# Device_1_ver1_1.net
KiCad netlist of a schematic drawn in EAGLE
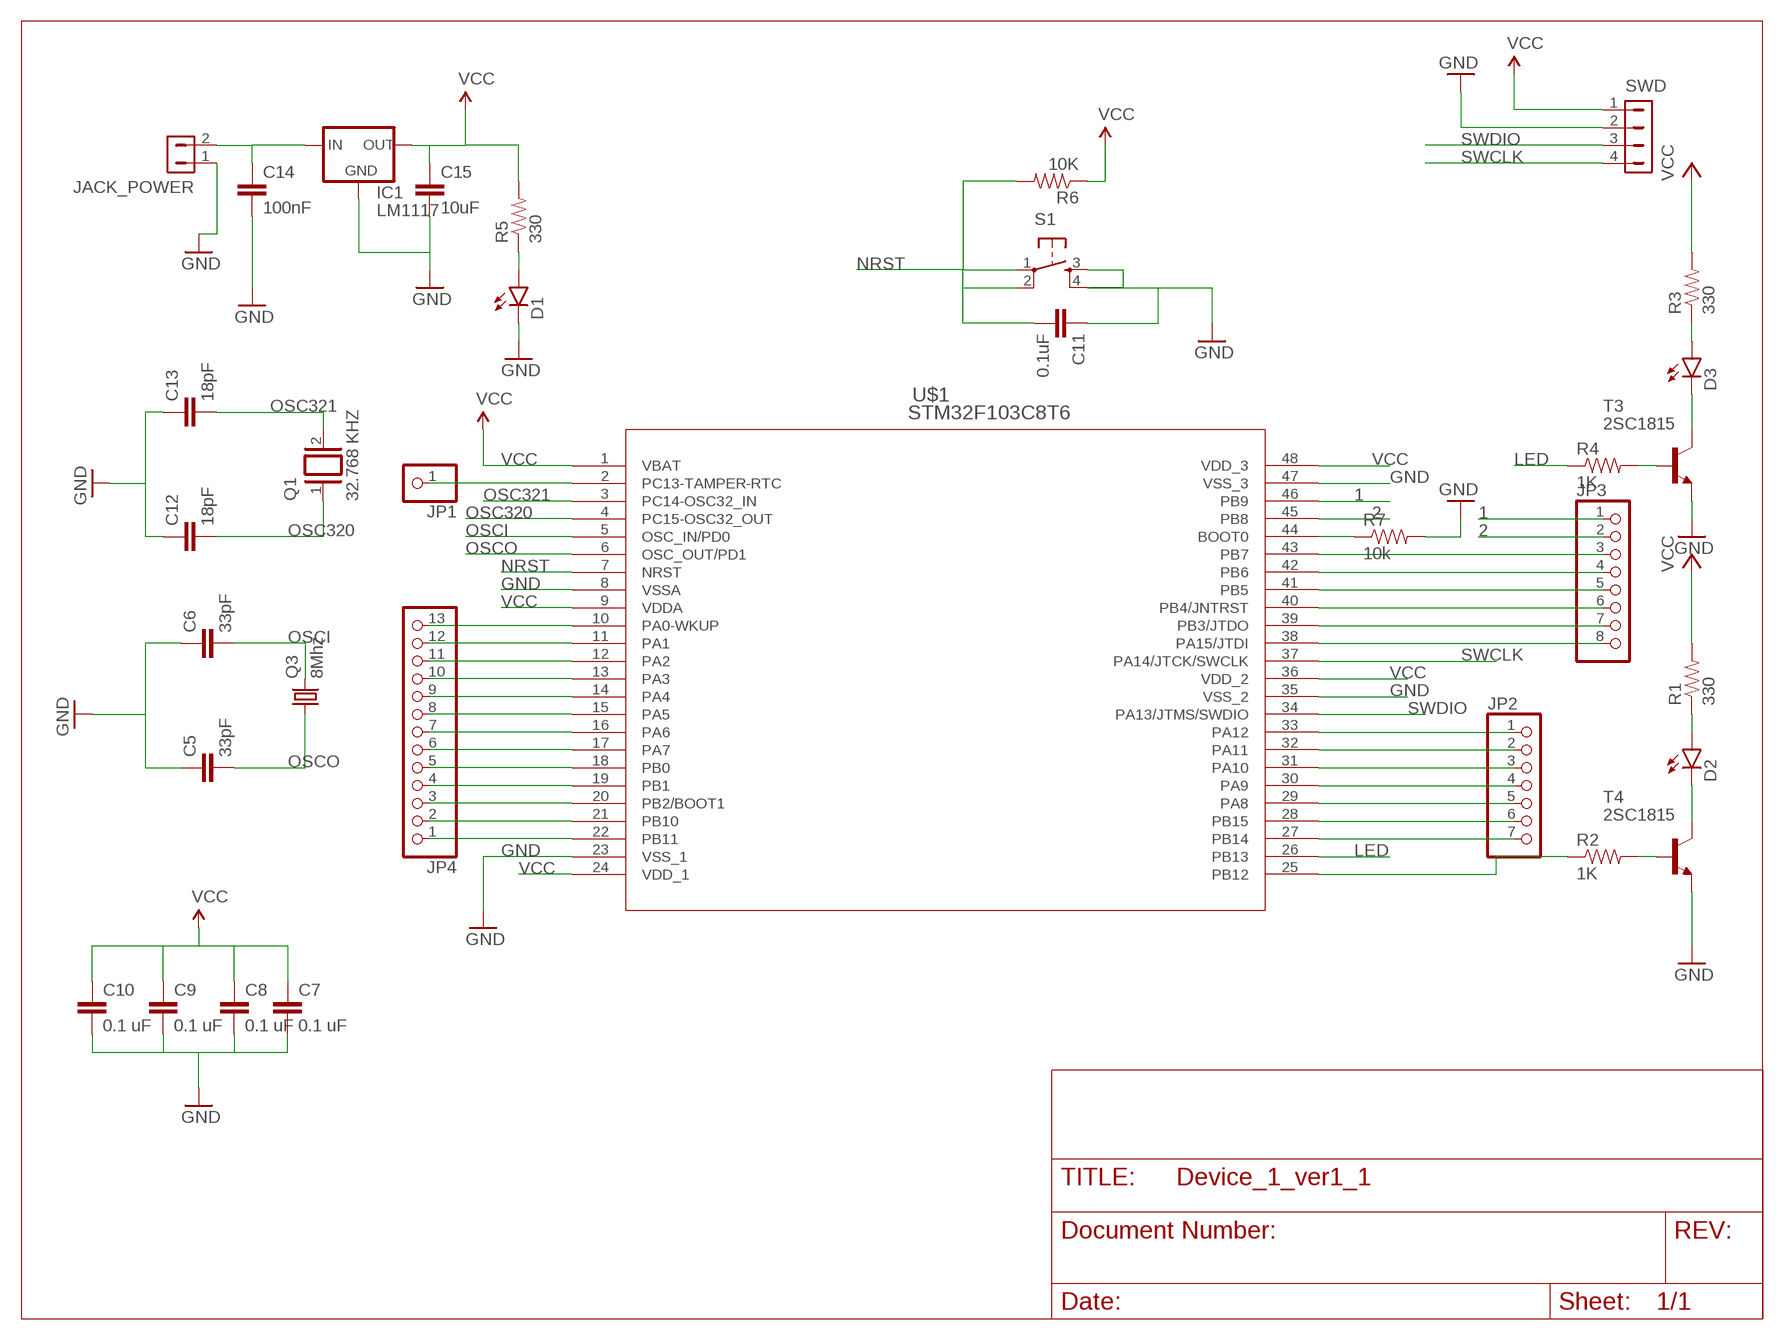
[diagram p0: schematic, sheet 1]

(export (version "E")
  (design (tool "Eeschema 10.0.6"))
  (components
    (comp (ref "C5")
      (value "33pF")
      (footprint "eagle-import:CAP-PTH-SMALL")
      (libsource (lib "eagle-import") (part "CAPPTH"))
    )
    (comp (ref "C6")
      (value "33pF")
      (footprint "eagle-import:CAP-PTH-SMALL")
      (libsource (lib "eagle-import") (part "CAPPTH"))
    )
    (comp (ref "C7")
      (value "0.1 uF")
      (footprint "eagle-import:CAP-PTH-SMALL")
      (libsource (lib "eagle-import") (part "CAPPTH"))
    )
    (comp (ref "C8")
      (value "0.1 uF")
      (footprint "eagle-import:CAP-PTH-SMALL")
      (libsource (lib "eagle-import") (part "CAPPTH"))
    )
    (comp (ref "C9")
      (value "0.1 uF")
      (footprint "eagle-import:CAP-PTH-SMALL")
      (libsource (lib "eagle-import") (part "CAPPTH"))
    )
    (comp (ref "C10")
      (value "0.1 uF")
      (footprint "eagle-import:CAP-PTH-SMALL")
      (libsource (lib "eagle-import") (part "CAPPTH"))
    )
    (comp (ref "C11")
      (value "0.1uF")
      (footprint "eagle-import:CAP-PTH-SMALL")
      (libsource (lib "eagle-import") (part "CAPPTH"))
    )
    (comp (ref "C12")
      (value "18pF")
      (footprint "eagle-import:CAP-PTH-SMALL")
      (libsource (lib "eagle-import") (part "CAPPTH"))
    )
    (comp (ref "C13")
      (value "18pF")
      (footprint "eagle-import:CAP-PTH-SMALL")
      (libsource (lib "eagle-import") (part "CAPPTH"))
    )
    (comp (ref "C14")
      (value "100nF")
      (footprint "eagle-import:CAP-PTH-SMALL")
      (libsource (lib "eagle-import") (part "CAPPTH"))
    )
    (comp (ref "C15")
      (value "10uF")
      (footprint "eagle-import:CAP-PTH-SMALL")
      (libsource (lib "eagle-import") (part "CAPPTH"))
    )
    (comp (ref "D1")
      (value "LED5MM")
      (footprint "eagle-import:LED5MM")
      (libsource (lib "eagle-import") (part "LED5MM"))
    )
    (comp (ref "D2")
      (value "LED5MM")
      (footprint "eagle-import:LED5MM")
      (libsource (lib "eagle-import") (part "LED5MM"))
    )
    (comp (ref "D3")
      (value "LED5MM")
      (footprint "eagle-import:LED5MM")
      (libsource (lib "eagle-import") (part "LED5MM"))
    )
    (comp (ref "IC1")
      (value "LM1117")
      (footprint "eagle-import:SOT223")
      (libsource (lib "eagle-import") (part "LM1117"))
    )
    (comp (ref "JACK_POWER")
      (value "HDR-1X2-MTE-100")
      (footprint "eagle-import:MTE-100-2V")
      (libsource (lib "eagle-import") (part "HDR-1X2-MTE-100"))
    )
    (comp (ref "JP1")
      (value "PINHD-1X1")
      (footprint "eagle-import:1X01")
      (libsource (lib "eagle-import") (part "PINHD-1X1"))
    )
    (comp (ref "JP2")
      (value "PINHD-1X7")
      (footprint "eagle-import:1X07")
      (libsource (lib "eagle-import") (part "PINHD-1X7"))
    )
    (comp (ref "JP3")
      (value "PINHD-1X8")
      (footprint "eagle-import:1X08")
      (libsource (lib "eagle-import") (part "PINHD-1X8"))
    )
    (comp (ref "JP4")
      (value "PINHD-1X13")
      (footprint "eagle-import:1X13")
      (libsource (lib "eagle-import") (part "PINHD-1X13"))
    )
    (comp (ref "Q1")
      (value "32.768 KHZ")
      (footprint "eagle-import:QS")
      (libsource (lib "eagle-import") (part "XTAL/S"))
    )
    (comp (ref "Q3")
      (value "8Mhz")
      (footprint "eagle-import:HC49_S")
      (libsource (lib "eagle-import") (part "CRYSTALHC49S"))
    )
    (comp (ref "R1")
      (value "330")
      (footprint "eagle-import:AXIAL-0.4")
      (libsource (lib "eagle-import") (part "RESISTORPTH-1/4W"))
    )
    (comp (ref "R2")
      (value "1K")
      (footprint "eagle-import:AXIAL-0.4")
      (libsource (lib "eagle-import") (part "RESISTORPTH-1/4W"))
    )
    (comp (ref "R3")
      (value "330")
      (footprint "eagle-import:AXIAL-0.4")
      (libsource (lib "eagle-import") (part "RESISTORPTH-1/4W"))
    )
    (comp (ref "R4")
      (value "1K")
      (footprint "eagle-import:AXIAL-0.4")
      (libsource (lib "eagle-import") (part "RESISTORPTH-1/4W"))
    )
    (comp (ref "R5")
      (value "330")
      (footprint "eagle-import:AXIAL-0.4")
      (libsource (lib "eagle-import") (part "RESISTORPTH-1/4W"))
    )
    (comp (ref "R6")
      (value "10K")
      (footprint "eagle-import:AXIAL-0.4")
      (libsource (lib "eagle-import") (part "RESISTORPTH-1/4W"))
    )
    (comp (ref "R7")
      (value "10k")
      (footprint "eagle-import:AXIAL-0.4")
      (libsource (lib "eagle-import") (part "RESISTORPTH-1/4W"))
    )
    (comp (ref "S1")
      (value "TAC_SWITCHPTH")
      (footprint "eagle-import:TACTILE-PTH")
      (libsource (lib "eagle-import") (part "TAC_SWITCHPTH"))
    )
    (comp (ref "SWD")
      (value "HDR-1X4-MTE-100")
      (footprint "eagle-import:MTE-100-4V")
      (libsource (lib "eagle-import") (part "HDR-1X4-MTE-100"))
    )
    (comp (ref "T3")
      (value "2SC1815")
      (footprint "eagle-import:TO92-ECB")
      (libsource (lib "eagle-import") (part "2SC1815"))
    )
    (comp (ref "T4")
      (value "2SC1815")
      (footprint "eagle-import:TO92-ECB")
      (libsource (lib "eagle-import") (part "2SC1815"))
    )
    (comp (ref "U$1")
      (value "STM32F103C8T6")
      (footprint "eagle-import:LQFP48")
      (fields
        (field (name "DIGIKEYPARTNUMBER") "497-6063-ND")
        (field (name "COPYRIGHT") "Copyright (C) 2015 Accelerated Designs. All rights reserved")
      )
      (libsource (lib "eagle-import") (part "STM32F103C8T6"))
    )
  )
  (nets
    (net (code "1") (name "/1") (class "Default")
      (node (ref "JP3") (pin "1") (pinfunction "1_1") (pintype "passive"))
      (node (ref "U$1") (pin "46") (pinfunction "PB9_46") (pintype "bidirectional"))
    )
    (net (code "2") (name "/2") (class "Default")
      (node (ref "JP3") (pin "2") (pinfunction "2_2") (pintype "passive"))
      (node (ref "U$1") (pin "45") (pinfunction "PB8_45") (pintype "bidirectional"))
    )
    (net (code "3") (name "/LED") (class "Default")
      (node (ref "R4") (pin "P$1") (pinfunction "1_P$1") (pintype "passive"))
      (node (ref "U$1") (pin "26") (pinfunction "PB13_26") (pintype "bidirectional"))
    )
    (net (code "4") (name "/NRST") (class "Default")
      (node (ref "C11") (pin "2") (pinfunction "2_2") (pintype "passive"))
      (node (ref "R6") (pin "P$2") (pinfunction "2_P$2") (pintype "passive"))
      (node (ref "S1") (pin "1") (pinfunction "1_1") (pintype "passive"))
      (node (ref "S1") (pin "2") (pinfunction "2_2") (pintype "passive"))
      (node (ref "U$1") (pin "7") (pinfunction "NRST_7") (pintype "bidirectional"))
    )
    (net (code "5") (name "/OSC320") (class "Default")
      (node (ref "C12") (pin "2") (pinfunction "2_2") (pintype "passive"))
      (node (ref "Q1") (pin "1") (pinfunction "1_1") (pintype "passive"))
      (node (ref "U$1") (pin "4") (pinfunction "PC15-OSC32_OUT_4") (pintype "bidirectional"))
    )
    (net (code "6") (name "/OSC321") (class "Default")
      (node (ref "C13") (pin "2") (pinfunction "2_2") (pintype "passive"))
      (node (ref "Q1") (pin "2") (pinfunction "2_2") (pintype "passive"))
      (node (ref "U$1") (pin "3") (pinfunction "PC14-OSC32_IN_3") (pintype "bidirectional"))
    )
    (net (code "7") (name "/OSCI") (class "Default")
      (node (ref "C6") (pin "2") (pinfunction "2_2") (pintype "passive"))
      (node (ref "Q3") (pin "2") (pinfunction "2_2") (pintype "passive"))
      (node (ref "U$1") (pin "5") (pinfunction "OSC_IN/PD0_5") (pintype "input"))
    )
    (net (code "8") (name "/OSCO") (class "Default")
      (node (ref "C5") (pin "2") (pinfunction "2_2") (pintype "passive"))
      (node (ref "Q3") (pin "1") (pinfunction "1_1") (pintype "passive"))
      (node (ref "U$1") (pin "6") (pinfunction "OSC_OUT/PD1_6") (pintype "output"))
    )
    (net (code "9") (name "/SWCLK") (class "Default")
      (node (ref "SWD") (pin "4") (pinfunction "4_4") (pintype "passive"))
      (node (ref "U$1") (pin "37") (pinfunction "PA14/JTCK/SWCLK_37") (pintype "bidirectional"))
    )
    (net (code "10") (name "/SWDIO") (class "Default")
      (node (ref "SWD") (pin "3") (pinfunction "3_3") (pintype "passive"))
      (node (ref "U$1") (pin "34") (pinfunction "PA13/JTMS/SWDIO_34") (pintype "bidirectional"))
    )
    (net (code "11") (name "GND") (class "Default")
      (node (ref "C10") (pin "2") (pinfunction "2_2") (pintype "passive"))
      (node (ref "C11") (pin "1") (pinfunction "1_1") (pintype "passive"))
      (node (ref "C12") (pin "1") (pinfunction "1_1") (pintype "passive"))
      (node (ref "C13") (pin "1") (pinfunction "1_1") (pintype "passive"))
      (node (ref "C14") (pin "2") (pinfunction "2_2") (pintype "passive"))
      (node (ref "C15") (pin "2") (pinfunction "2_2") (pintype "passive"))
      (node (ref "C5") (pin "1") (pinfunction "1_1") (pintype "passive"))
      (node (ref "C6") (pin "1") (pinfunction "1_1") (pintype "passive"))
      (node (ref "C7") (pin "2") (pinfunction "2_2") (pintype "passive"))
      (node (ref "C8") (pin "2") (pinfunction "2_2") (pintype "passive"))
      (node (ref "C9") (pin "2") (pinfunction "2_2") (pintype "passive"))
      (node (ref "D1") (pin "K") (pinfunction "C_K") (pintype "passive"))
      (node (ref "IC1") (pin "1") (pinfunction "GND_1") (pintype "input"))
      (node (ref "JACK_POWER") (pin "1") (pinfunction "1_1") (pintype "passive"))
      (node (ref "R7") (pin "P$2") (pinfunction "2_P$2") (pintype "passive"))
      (node (ref "S1") (pin "3") (pinfunction "3_3") (pintype "passive"))
      (node (ref "S1") (pin "4") (pinfunction "4_4") (pintype "passive"))
      (node (ref "SWD") (pin "2") (pinfunction "2_2") (pintype "passive"))
      (node (ref "T3") (pin "E") (pinfunction "E_E") (pintype "passive"))
      (node (ref "T4") (pin "E") (pinfunction "E_E") (pintype "passive"))
      (node (ref "U$1") (pin "23") (pinfunction "VSS_1_23") (pintype "power_in"))
      (node (ref "U$1") (pin "35") (pinfunction "VSS_2_35") (pintype "power_in"))
      (node (ref "U$1") (pin "47") (pinfunction "VSS_3_47") (pintype "power_in"))
      (node (ref "U$1") (pin "8") (pinfunction "VSSA_8") (pintype "power_in"))
    )
    (net (code "12") (name "Net-(D2-C)") (class "Default")
      (node (ref "D2") (pin "K") (pinfunction "C_K") (pintype "passive"))
      (node (ref "T4") (pin "C") (pinfunction "C_C") (pintype "passive"))
    )
    (net (code "13") (name "Net-(D3-C)") (class "Default")
      (node (ref "D3") (pin "K") (pinfunction "C_K") (pintype "passive"))
      (node (ref "T3") (pin "C") (pinfunction "C_C") (pintype "passive"))
    )
    (net (code "14") (name "Net-(IC1-IN)") (class "Default")
      (node (ref "C14") (pin "1") (pinfunction "1_1") (pintype "passive"))
      (node (ref "IC1") (pin "3") (pinfunction "IN_3") (pintype "input"))
      (node (ref "JACK_POWER") (pin "2") (pinfunction "2_2") (pintype "passive"))
    )
    (net (code "15") (name "Net-(R1-1)") (class "Default")
      (node (ref "D2") (pin "A") (pinfunction "A_A") (pintype "passive"))
      (node (ref "R1") (pin "P$1") (pinfunction "1_P$1") (pintype "passive"))
    )
    (net (code "16") (name "Net-(R2-1)") (class "Default")
      (node (ref "R2") (pin "P$1") (pinfunction "1_P$1") (pintype "passive"))
      (node (ref "U$1") (pin "25") (pinfunction "PB12_25") (pintype "bidirectional"))
    )
    (net (code "17") (name "Net-(R2-2)") (class "Default")
      (node (ref "R2") (pin "P$2") (pinfunction "2_P$2") (pintype "passive"))
      (node (ref "T4") (pin "B") (pinfunction "B_B") (pintype "passive"))
    )
    (net (code "18") (name "Net-(R3-1)") (class "Default")
      (node (ref "D3") (pin "A") (pinfunction "A_A") (pintype "passive"))
      (node (ref "R3") (pin "P$1") (pinfunction "1_P$1") (pintype "passive"))
    )
    (net (code "19") (name "Net-(R4-2)") (class "Default")
      (node (ref "R4") (pin "P$2") (pinfunction "2_P$2") (pintype "passive"))
      (node (ref "T3") (pin "B") (pinfunction "B_B") (pintype "passive"))
    )
    (net (code "20") (name "Net-(R5-1)") (class "Default")
      (node (ref "D1") (pin "A") (pinfunction "A_A") (pintype "passive"))
      (node (ref "R5") (pin "P$1") (pinfunction "1_P$1") (pintype "passive"))
    )
    (net (code "21") (name "Net-(R7-1)") (class "Default")
      (node (ref "R7") (pin "P$1") (pinfunction "1_P$1") (pintype "passive"))
      (node (ref "U$1") (pin "44") (pinfunction "BOOT0_44") (pintype "input"))
    )
    (net (code "22") (name "Net-(U$1-PA0-WKUP)") (class "Default")
      (node (ref "JP4") (pin "13") (pinfunction "13_13") (pintype "passive"))
      (node (ref "U$1") (pin "10") (pinfunction "PA0-WKUP_10") (pintype "bidirectional"))
    )
    (net (code "23") (name "Net-(U$1-PA1)") (class "Default")
      (node (ref "JP4") (pin "12") (pinfunction "12_12") (pintype "passive"))
      (node (ref "U$1") (pin "11") (pinfunction "PA1_11") (pintype "bidirectional"))
    )
    (net (code "24") (name "Net-(U$1-PA2)") (class "Default")
      (node (ref "JP4") (pin "11") (pinfunction "11_11") (pintype "passive"))
      (node (ref "U$1") (pin "12") (pinfunction "PA2_12") (pintype "bidirectional"))
    )
    (net (code "25") (name "Net-(U$1-PA3)") (class "Default")
      (node (ref "JP4") (pin "10") (pinfunction "10_10") (pintype "passive"))
      (node (ref "U$1") (pin "13") (pinfunction "PA3_13") (pintype "bidirectional"))
    )
    (net (code "26") (name "Net-(U$1-PA4)") (class "Default")
      (node (ref "JP4") (pin "9") (pinfunction "9_9") (pintype "passive"))
      (node (ref "U$1") (pin "14") (pinfunction "PA4_14") (pintype "bidirectional"))
    )
    (net (code "27") (name "Net-(U$1-PA5)") (class "Default")
      (node (ref "JP4") (pin "8") (pinfunction "8_8") (pintype "passive"))
      (node (ref "U$1") (pin "15") (pinfunction "PA5_15") (pintype "bidirectional"))
    )
    (net (code "28") (name "Net-(U$1-PA6)") (class "Default")
      (node (ref "JP4") (pin "7") (pinfunction "7_7") (pintype "passive"))
      (node (ref "U$1") (pin "16") (pinfunction "PA6_16") (pintype "bidirectional"))
    )
    (net (code "29") (name "Net-(U$1-PA7)") (class "Default")
      (node (ref "JP4") (pin "6") (pinfunction "6_6") (pintype "passive"))
      (node (ref "U$1") (pin "17") (pinfunction "PA7_17") (pintype "bidirectional"))
    )
    (net (code "30") (name "Net-(U$1-PA8)") (class "Default")
      (node (ref "JP2") (pin "5") (pinfunction "5_5") (pintype "passive"))
      (node (ref "U$1") (pin "29") (pinfunction "PA8_29") (pintype "bidirectional"))
    )
    (net (code "31") (name "Net-(U$1-PA9)") (class "Default")
      (node (ref "JP2") (pin "4") (pinfunction "4_4") (pintype "passive"))
      (node (ref "U$1") (pin "30") (pinfunction "PA9_30") (pintype "bidirectional"))
    )
    (net (code "32") (name "Net-(U$1-PA10)") (class "Default")
      (node (ref "JP2") (pin "3") (pinfunction "3_3") (pintype "passive"))
      (node (ref "U$1") (pin "31") (pinfunction "PA10_31") (pintype "bidirectional"))
    )
    (net (code "33") (name "Net-(U$1-PA11)") (class "Default")
      (node (ref "JP2") (pin "2") (pinfunction "2_2") (pintype "passive"))
      (node (ref "U$1") (pin "32") (pinfunction "PA11_32") (pintype "bidirectional"))
    )
    (net (code "34") (name "Net-(U$1-PA12)") (class "Default")
      (node (ref "JP2") (pin "1") (pinfunction "1_1") (pintype "passive"))
      (node (ref "U$1") (pin "33") (pinfunction "PA12_33") (pintype "bidirectional"))
    )
    (net (code "35") (name "Net-(U$1-PA15{slash}JTDI)") (class "Default")
      (node (ref "JP3") (pin "8") (pinfunction "8_8") (pintype "passive"))
      (node (ref "U$1") (pin "38") (pinfunction "PA15/JTDI_38") (pintype "bidirectional"))
    )
    (net (code "36") (name "Net-(U$1-PB0)") (class "Default")
      (node (ref "JP4") (pin "5") (pinfunction "5_5") (pintype "passive"))
      (node (ref "U$1") (pin "18") (pinfunction "PB0_18") (pintype "bidirectional"))
    )
    (net (code "37") (name "Net-(U$1-PB1)") (class "Default")
      (node (ref "JP4") (pin "4") (pinfunction "4_4") (pintype "passive"))
      (node (ref "U$1") (pin "19") (pinfunction "PB1_19") (pintype "bidirectional"))
    )
    (net (code "38") (name "Net-(U$1-PB2{slash}BOOT1)") (class "Default")
      (node (ref "JP4") (pin "3") (pinfunction "3_3") (pintype "passive"))
      (node (ref "U$1") (pin "20") (pinfunction "PB2/BOOT1_20") (pintype "bidirectional"))
    )
    (net (code "39") (name "Net-(U$1-PB3{slash}JTDO)") (class "Default")
      (node (ref "JP3") (pin "7") (pinfunction "7_7") (pintype "passive"))
      (node (ref "U$1") (pin "39") (pinfunction "PB3/JTDO_39") (pintype "bidirectional"))
    )
    (net (code "40") (name "Net-(U$1-PB4{slash}JNTRST)") (class "Default")
      (node (ref "JP3") (pin "6") (pinfunction "6_6") (pintype "passive"))
      (node (ref "U$1") (pin "40") (pinfunction "PB4/JNTRST_40") (pintype "bidirectional"))
    )
    (net (code "41") (name "Net-(U$1-PB5)") (class "Default")
      (node (ref "JP3") (pin "5") (pinfunction "5_5") (pintype "passive"))
      (node (ref "U$1") (pin "41") (pinfunction "PB5_41") (pintype "bidirectional"))
    )
    (net (code "42") (name "Net-(U$1-PB6)") (class "Default")
      (node (ref "JP3") (pin "4") (pinfunction "4_4") (pintype "passive"))
      (node (ref "U$1") (pin "42") (pinfunction "PB6_42") (pintype "bidirectional"))
    )
    (net (code "43") (name "Net-(U$1-PB7)") (class "Default")
      (node (ref "JP3") (pin "3") (pinfunction "3_3") (pintype "passive"))
      (node (ref "U$1") (pin "43") (pinfunction "PB7_43") (pintype "bidirectional"))
    )
    (net (code "44") (name "Net-(U$1-PB10)") (class "Default")
      (node (ref "JP4") (pin "2") (pinfunction "2_2") (pintype "passive"))
      (node (ref "U$1") (pin "21") (pinfunction "PB10_21") (pintype "bidirectional"))
    )
    (net (code "45") (name "Net-(U$1-PB11)") (class "Default")
      (node (ref "JP4") (pin "1") (pinfunction "1_1") (pintype "passive"))
      (node (ref "U$1") (pin "22") (pinfunction "PB11_22") (pintype "bidirectional"))
    )
    (net (code "46") (name "Net-(U$1-PB14)") (class "Default")
      (node (ref "JP2") (pin "7") (pinfunction "7_7") (pintype "passive"))
      (node (ref "U$1") (pin "27") (pinfunction "PB14_27") (pintype "bidirectional"))
    )
    (net (code "47") (name "Net-(U$1-PB15)") (class "Default")
      (node (ref "JP2") (pin "6") (pinfunction "6_6") (pintype "passive"))
      (node (ref "U$1") (pin "28") (pinfunction "PB15_28") (pintype "bidirectional"))
    )
    (net (code "48") (name "Net-(U$1-PC13-TAMPER-RTC)") (class "Default")
      (node (ref "JP1") (pin "1") (pinfunction "1_1") (pintype "passive"))
      (node (ref "U$1") (pin "2") (pinfunction "PC13-TAMPER-RTC_2") (pintype "bidirectional"))
    )
    (net (code "49") (name "VCC") (class "Default")
      (node (ref "C10") (pin "1") (pinfunction "1_1") (pintype "passive"))
      (node (ref "C15") (pin "1") (pinfunction "1_1") (pintype "passive"))
      (node (ref "C7") (pin "1") (pinfunction "1_1") (pintype "passive"))
      (node (ref "C8") (pin "1") (pinfunction "1_1") (pintype "passive"))
      (node (ref "C9") (pin "1") (pinfunction "1_1") (pintype "passive"))
      (node (ref "IC1") (pin "2") (pinfunction "OUT_2") (pintype "passive"))
      (node (ref "R1") (pin "P$2") (pinfunction "2_P$2") (pintype "passive"))
      (node (ref "R3") (pin "P$2") (pinfunction "2_P$2") (pintype "passive"))
      (node (ref "R5") (pin "P$2") (pinfunction "2_P$2") (pintype "passive"))
      (node (ref "R6") (pin "P$1") (pinfunction "1_P$1") (pintype "passive"))
      (node (ref "SWD") (pin "1") (pinfunction "1_1") (pintype "passive"))
      (node (ref "U$1") (pin "1") (pinfunction "VBAT_1") (pintype "power_in"))
      (node (ref "U$1") (pin "24") (pinfunction "VDD_1_24") (pintype "power_in"))
      (node (ref "U$1") (pin "36") (pinfunction "VDD_2_36") (pintype "power_in"))
      (node (ref "U$1") (pin "48") (pinfunction "VDD_3_48") (pintype "power_in"))
      (node (ref "U$1") (pin "9") (pinfunction "VDDA_9") (pintype "power_in"))
    )
  )
)
